# HAN_DE10-Lite_PS2SpeakerShield_001.net
KiCad netlist of a schematic drawn in EAGLE
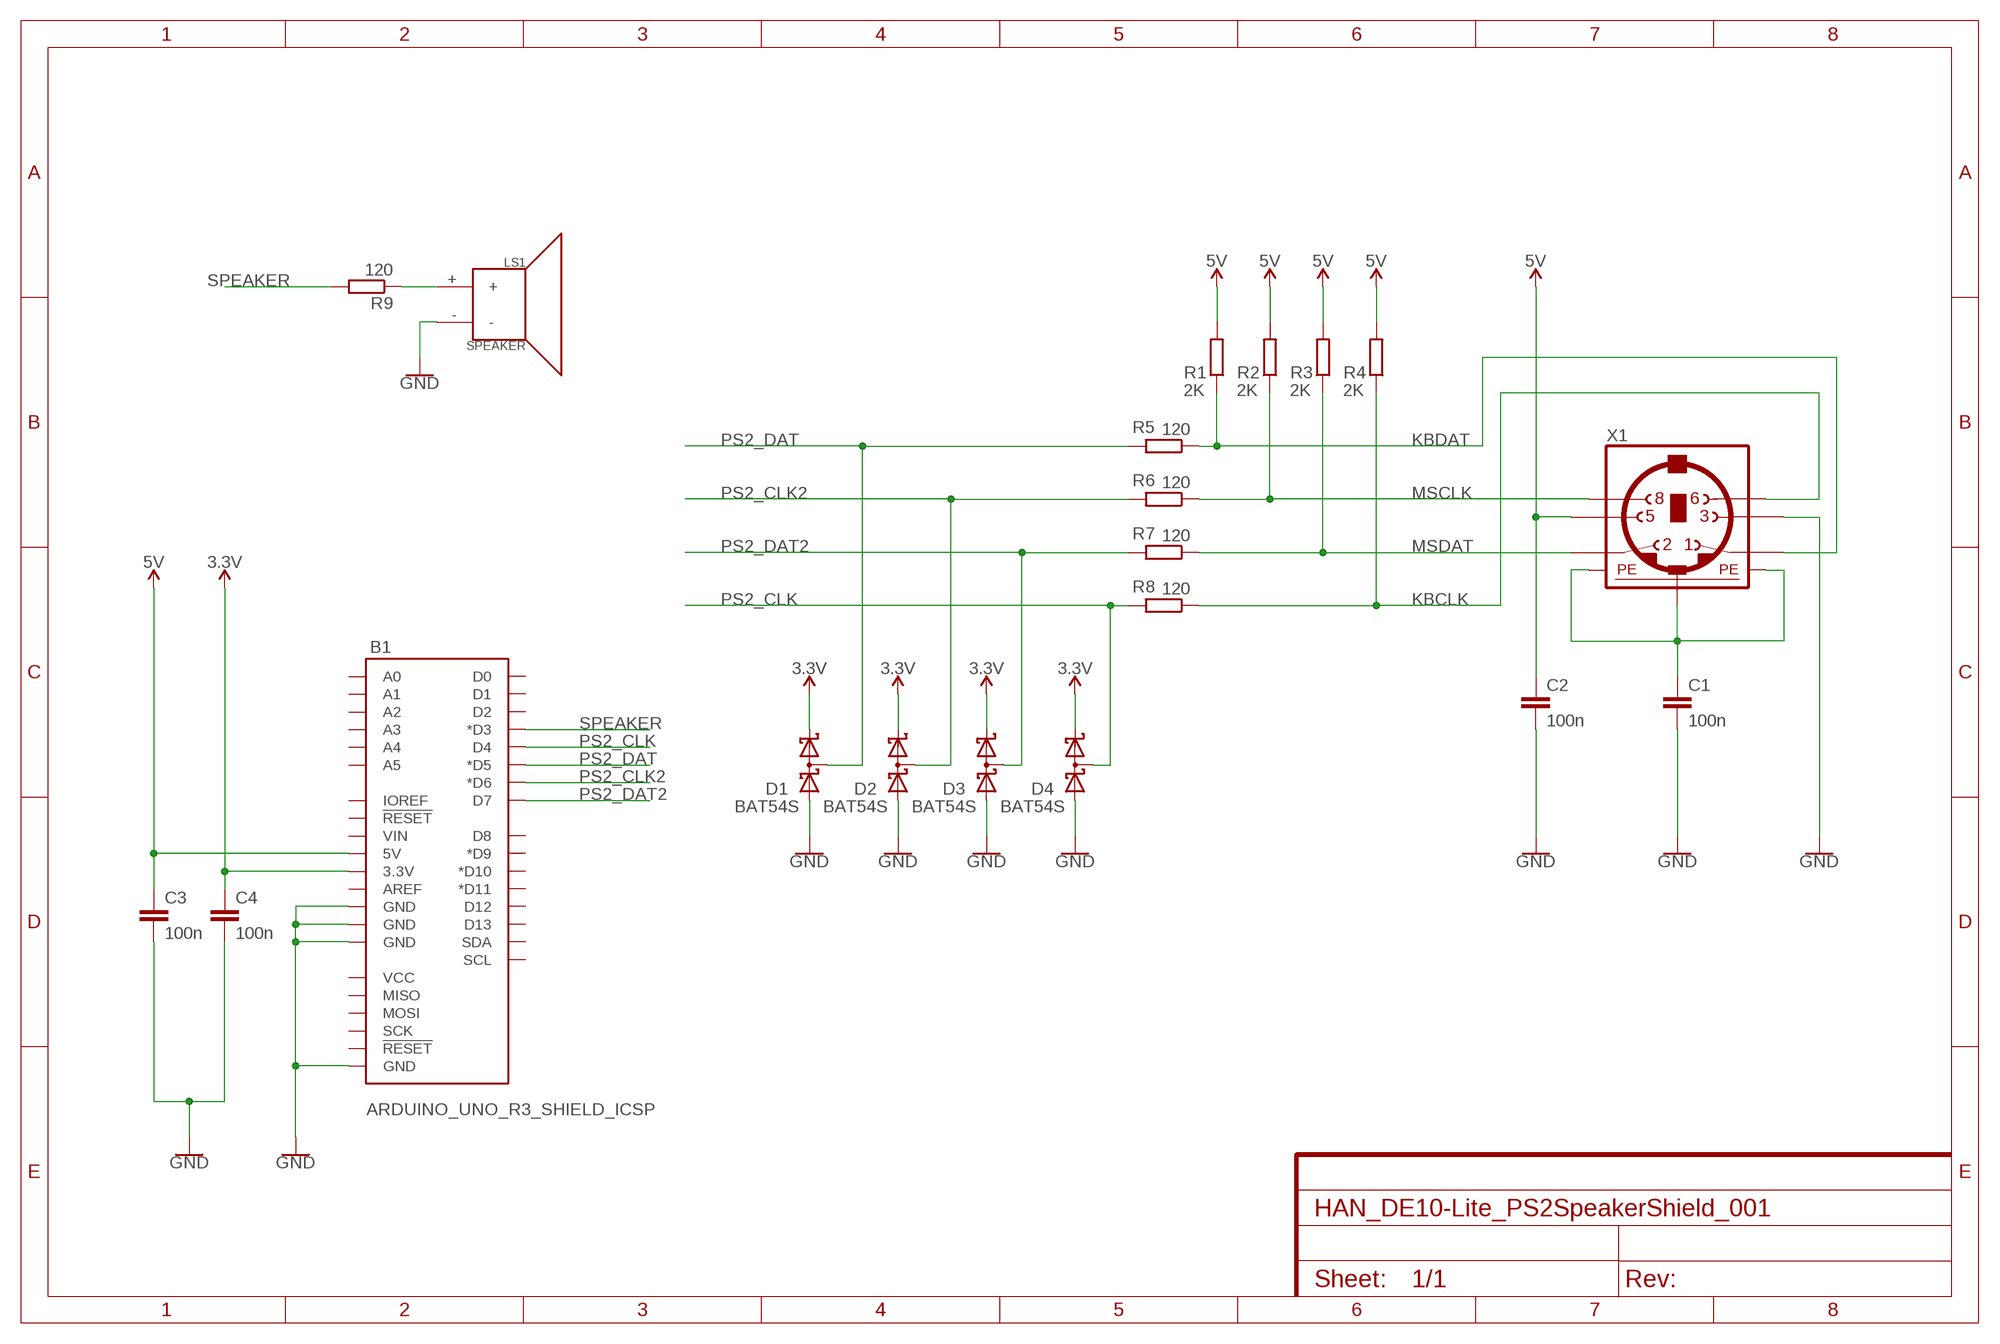
[diagram p0: schematic, sheet 1]

(export (version "E")
  (design (tool "Eeschema 10.0.6"))
  (components
    (comp (ref "B1")
      (value "ARDUINO_UNO_R3_SHIELD_ICSP")
      (footprint "eagle-import:UNO_R3_SHIELD_ICSP")
      (libsource (lib "eagle-import") (part "ARDUINO_UNO_R3_SHIELD_ICSP"))
    )
    (comp (ref "C1")
      (value "100n")
      (footprint "eagle-import:C1206")
      (libsource (lib "eagle-import") (part "C-EUC1206"))
    )
    (comp (ref "C2")
      (value "100n")
      (footprint "eagle-import:C1206")
      (libsource (lib "eagle-import") (part "C-EUC1206"))
    )
    (comp (ref "C3")
      (value "100n")
      (footprint "eagle-import:C1206")
      (libsource (lib "eagle-import") (part "C-EUC1206"))
    )
    (comp (ref "C4")
      (value "100n")
      (footprint "eagle-import:C1206")
      (libsource (lib "eagle-import") (part "C-EUC1206"))
    )
    (comp (ref "D1")
      (value "BAT54S")
      (footprint "eagle-import:SOT23")
      (libsource (lib "eagle-import") (part "BAT54S"))
    )
    (comp (ref "D2")
      (value "BAT54S")
      (footprint "eagle-import:SOT23")
      (libsource (lib "eagle-import") (part "BAT54S"))
    )
    (comp (ref "D3")
      (value "BAT54S")
      (footprint "eagle-import:SOT23")
      (libsource (lib "eagle-import") (part "BAT54S"))
    )
    (comp (ref "D4")
      (value "BAT54S")
      (footprint "eagle-import:SOT23")
      (libsource (lib "eagle-import") (part "BAT54S"))
    )
    (comp (ref "LS1")
      (value "SPEAKER")
      (footprint "eagle-import:PCB_MOUNT_SPEAKER")
      (libsource (lib "eagle-import") (part "SPEAKER"))
    )
    (comp (ref "R1")
      (value "2K")
      (footprint "eagle-import:M1206")
      (libsource (lib "eagle-import") (part "R-EU_M1206"))
    )
    (comp (ref "R2")
      (value "2K")
      (footprint "eagle-import:M1206")
      (libsource (lib "eagle-import") (part "R-EU_M1206"))
    )
    (comp (ref "R3")
      (value "2K")
      (footprint "eagle-import:M1206")
      (libsource (lib "eagle-import") (part "R-EU_M1206"))
    )
    (comp (ref "R4")
      (value "2K")
      (footprint "eagle-import:M1206")
      (libsource (lib "eagle-import") (part "R-EU_M1206"))
    )
    (comp (ref "R5")
      (value "120")
      (footprint "eagle-import:M1206")
      (libsource (lib "eagle-import") (part "R-EU_M1206"))
    )
    (comp (ref "R6")
      (value "120")
      (footprint "eagle-import:M1206")
      (libsource (lib "eagle-import") (part "R-EU_M1206"))
    )
    (comp (ref "R7")
      (value "120")
      (footprint "eagle-import:M1206")
      (libsource (lib "eagle-import") (part "R-EU_M1206"))
    )
    (comp (ref "R8")
      (value "120")
      (footprint "eagle-import:M1206")
      (libsource (lib "eagle-import") (part "R-EU_M1206"))
    )
    (comp (ref "R9")
      (value "120")
      (footprint "eagle-import:M1206")
      (libsource (lib "eagle-import") (part "R-EU_M1206"))
    )
    (comp (ref "X1")
      (value "MINI_DIN_6")
      (footprint "eagle-import:M_DIN6")
      (libsource (lib "eagle-import") (part "MINI_DIN_6"))
    )
  )
  (nets
    (net (code "1") (name "/KBCLK") (class "Default")
      (node (ref "R4") (pin "1") (pinfunction "1_1") (pintype "passive"))
      (node (ref "R8") (pin "1") (pinfunction "1_1") (pintype "passive"))
      (node (ref "X1") (pin "6") (pinfunction "6_6") (pintype "passive"))
    )
    (net (code "2") (name "/KBDAT") (class "Default")
      (node (ref "R1") (pin "1") (pinfunction "1_1") (pintype "passive"))
      (node (ref "R5") (pin "1") (pinfunction "1_1") (pintype "passive"))
      (node (ref "X1") (pin "1") (pinfunction "1_1") (pintype "passive"))
    )
    (net (code "3") (name "/MSCLK") (class "Default")
      (node (ref "R2") (pin "1") (pinfunction "1_1") (pintype "passive"))
      (node (ref "R6") (pin "1") (pinfunction "1_1") (pintype "passive"))
      (node (ref "X1") (pin "8") (pinfunction "8_8") (pintype "passive"))
    )
    (net (code "4") (name "/MSDAT") (class "Default")
      (node (ref "R3") (pin "1") (pinfunction "1_1") (pintype "passive"))
      (node (ref "R7") (pin "1") (pinfunction "1_1") (pintype "passive"))
      (node (ref "X1") (pin "2") (pinfunction "2_2") (pintype "passive"))
    )
    (net (code "5") (name "/PS2_CLK") (class "Default")
      (node (ref "B1") (pin "D4") (pinfunction "D4_D4") (pintype "bidirectional"))
      (node (ref "D4") (pin "3") (pinfunction "K1A2_3") (pintype "passive"))
      (node (ref "R8") (pin "2") (pinfunction "2_2") (pintype "passive"))
    )
    (net (code "6") (name "/PS2_CLK2") (class "Default")
      (node (ref "B1") (pin "D6") (pinfunction "*D6_D6") (pintype "bidirectional"))
      (node (ref "D2") (pin "3") (pinfunction "K1A2_3") (pintype "passive"))
      (node (ref "R6") (pin "2") (pinfunction "2_2") (pintype "passive"))
    )
    (net (code "7") (name "/PS2_DAT") (class "Default")
      (node (ref "B1") (pin "D5") (pinfunction "*D5_D5") (pintype "bidirectional"))
      (node (ref "D1") (pin "3") (pinfunction "K1A2_3") (pintype "passive"))
      (node (ref "R5") (pin "2") (pinfunction "2_2") (pintype "passive"))
    )
    (net (code "8") (name "/PS2_DAT2") (class "Default")
      (node (ref "B1") (pin "D7") (pinfunction "D7_D7") (pintype "bidirectional"))
      (node (ref "D3") (pin "3") (pinfunction "K1A2_3") (pintype "passive"))
      (node (ref "R7") (pin "2") (pinfunction "2_2") (pintype "passive"))
    )
    (net (code "9") (name "/SPEAKER") (class "Default")
      (node (ref "B1") (pin "D3") (pinfunction "*D3_D3") (pintype "bidirectional"))
      (node (ref "R9") (pin "2") (pinfunction "2_2") (pintype "passive"))
    )
    (net (code "10") (name "3.3V") (class "Default")
      (node (ref "B1") (pin "3.3V") (pinfunction "3.3V_3.3V") (pintype "bidirectional"))
      (node (ref "C4") (pin "1") (pinfunction "1_1") (pintype "passive"))
      (node (ref "D1") (pin "2") (pinfunction "K2_2") (pintype "passive"))
      (node (ref "D2") (pin "2") (pinfunction "K2_2") (pintype "passive"))
      (node (ref "D3") (pin "2") (pinfunction "K2_2") (pintype "passive"))
      (node (ref "D4") (pin "2") (pinfunction "K2_2") (pintype "passive"))
    )
    (net (code "11") (name "5V") (class "Default")
      (node (ref "B1") (pin "5V") (pinfunction "5V_5V") (pintype "bidirectional"))
      (node (ref "C2") (pin "1") (pinfunction "1_1") (pintype "passive"))
      (node (ref "C3") (pin "1") (pinfunction "1_1") (pintype "passive"))
      (node (ref "R1") (pin "2") (pinfunction "2_2") (pintype "passive"))
      (node (ref "R2") (pin "2") (pinfunction "2_2") (pintype "passive"))
      (node (ref "R3") (pin "2") (pinfunction "2_2") (pintype "passive"))
      (node (ref "R4") (pin "2") (pinfunction "2_2") (pintype "passive"))
      (node (ref "X1") (pin "5") (pinfunction "5_5") (pintype "passive"))
    )
    (net (code "12") (name "GND") (class "Default")
      (node (ref "B1") (pin "GND@0") (pinfunction "GND_GND@0") (pintype "bidirectional"))
      (node (ref "B1") (pin "GND@1") (pinfunction "GND_GND@1") (pintype "bidirectional"))
      (node (ref "B1") (pin "GND@2") (pinfunction "GND_GND@2") (pintype "bidirectional"))
      (node (ref "B1") (pin "GND_ICSP") (pinfunction "GND_GND_ICSP") (pintype "bidirectional"))
      (node (ref "C1") (pin "2") (pinfunction "2_2") (pintype "passive"))
      (node (ref "C2") (pin "2") (pinfunction "2_2") (pintype "passive"))
      (node (ref "C3") (pin "2") (pinfunction "2_2") (pintype "passive"))
      (node (ref "C4") (pin "2") (pinfunction "2_2") (pintype "passive"))
      (node (ref "D1") (pin "1") (pinfunction "A1_1") (pintype "passive"))
      (node (ref "D2") (pin "1") (pinfunction "A1_1") (pintype "passive"))
      (node (ref "D3") (pin "1") (pinfunction "A1_1") (pintype "passive"))
      (node (ref "D4") (pin "1") (pinfunction "A1_1") (pintype "passive"))
      (node (ref "LS1") (pin "-") (pinfunction "-_-") (pintype "bidirectional"))
      (node (ref "X1") (pin "3") (pinfunction "3_3") (pintype "passive"))
    )
    (net (code "13") (name "Net-(LS1-Pad+)") (class "Default")
      (node (ref "LS1") (pin "+") (pinfunction "+_+") (pintype "bidirectional"))
      (node (ref "R9") (pin "1") (pinfunction "1_1") (pintype "passive"))
    )
    (net (code "14") (name "Net-(X1-PE1)") (class "Default")
      (node (ref "C1") (pin "1") (pinfunction "1_1") (pintype "passive"))
      (node (ref "X1") (pin "SH1") (pinfunction "PE1_SH1") (pintype "power_in"))
      (node (ref "X1") (pin "SH2") (pinfunction "PE2_SH2") (pintype "power_in"))
      (node (ref "X1") (pin "SH3") (pinfunction "PE3_SH3") (pintype "power_in"))
    )
    (net (code "15") (name "unconnected-(B1-*D9-PadD9)") (class "Default")
      (node (ref "B1") (pin "D9") (pinfunction "*D9_D9") (pintype "bidirectional"))
    )
    (net (code "16") (name "unconnected-(B1-*D10-PadD10)") (class "Default")
      (node (ref "B1") (pin "D10") (pinfunction "*D10_D10") (pintype "bidirectional"))
    )
    (net (code "17") (name "unconnected-(B1-*D11-PadD11)") (class "Default")
      (node (ref "B1") (pin "D11") (pinfunction "*D11_D11") (pintype "bidirectional"))
    )
    (net (code "18") (name "unconnected-(B1-D0-PadRX)") (class "Default")
      (node (ref "B1") (pin "RX") (pinfunction "D0_RX") (pintype "bidirectional"))
    )
    (net (code "19") (name "unconnected-(B1-D1-PadTX)") (class "Default")
      (node (ref "B1") (pin "TX") (pinfunction "D1_TX") (pintype "bidirectional"))
    )
    (net (code "20") (name "unconnected-(B1-PadA0)") (class "Default")
      (node (ref "B1") (pin "A0") (pinfunction "A0_A0") (pintype "bidirectional"))
    )
    (net (code "21") (name "unconnected-(B1-PadA1)") (class "Default")
      (node (ref "B1") (pin "A1") (pinfunction "A1_A1") (pintype "bidirectional"))
    )
    (net (code "22") (name "unconnected-(B1-PadA2)") (class "Default")
      (node (ref "B1") (pin "A2") (pinfunction "A2_A2") (pintype "bidirectional"))
    )
    (net (code "23") (name "unconnected-(B1-PadA3)") (class "Default")
      (node (ref "B1") (pin "A3") (pinfunction "A3_A3") (pintype "bidirectional"))
    )
    (net (code "24") (name "unconnected-(B1-PadA4)") (class "Default")
      (node (ref "B1") (pin "A4") (pinfunction "A4_A4") (pintype "bidirectional"))
    )
    (net (code "25") (name "unconnected-(B1-PadA5)") (class "Default")
      (node (ref "B1") (pin "A5") (pinfunction "A5_A5") (pintype "bidirectional"))
    )
    (net (code "26") (name "unconnected-(B1-PadAREF)") (class "Default")
      (node (ref "B1") (pin "AREF") (pinfunction "AREF_AREF") (pintype "bidirectional"))
    )
    (net (code "27") (name "unconnected-(B1-PadD2)") (class "Default")
      (node (ref "B1") (pin "D2") (pinfunction "D2_D2") (pintype "bidirectional"))
    )
    (net (code "28") (name "unconnected-(B1-PadD8)") (class "Default")
      (node (ref "B1") (pin "D8") (pinfunction "D8_D8") (pintype "bidirectional"))
    )
    (net (code "29") (name "unconnected-(B1-PadD12)") (class "Default")
      (node (ref "B1") (pin "D12") (pinfunction "D12_D12") (pintype "bidirectional"))
    )
    (net (code "30") (name "unconnected-(B1-PadD13)") (class "Default")
      (node (ref "B1") (pin "D13") (pinfunction "D13_D13") (pintype "bidirectional"))
    )
    (net (code "31") (name "unconnected-(B1-PadIOREF)") (class "Default")
      (node (ref "B1") (pin "IOREF") (pinfunction "IOREF_IOREF") (pintype "bidirectional"))
    )
    (net (code "32") (name "unconnected-(B1-PadMISO)") (class "Default")
      (node (ref "B1") (pin "MISO") (pinfunction "MISO_MISO") (pintype "bidirectional"))
    )
    (net (code "33") (name "unconnected-(B1-PadMOSI)") (class "Default")
      (node (ref "B1") (pin "MOSI") (pinfunction "MOSI_MOSI") (pintype "bidirectional"))
    )
    (net (code "34") (name "unconnected-(B1-PadSCK)") (class "Default")
      (node (ref "B1") (pin "SCK") (pinfunction "SCK_SCK") (pintype "bidirectional"))
    )
    (net (code "35") (name "unconnected-(B1-PadSCL)") (class "Default")
      (node (ref "B1") (pin "SCL") (pinfunction "SCL_SCL") (pintype "bidirectional"))
    )
    (net (code "36") (name "unconnected-(B1-PadSDA)") (class "Default")
      (node (ref "B1") (pin "SDA") (pinfunction "SDA_SDA") (pintype "bidirectional"))
    )
    (net (code "37") (name "unconnected-(B1-PadVIN)") (class "Default")
      (node (ref "B1") (pin "VIN") (pinfunction "VIN_VIN") (pintype "bidirectional"))
    )
    (net (code "38") (name "unconnected-(B1-VCC-Pad5V_ICSP)") (class "Default")
      (node (ref "B1") (pin "5V_ICSP") (pinfunction "VCC_5V_ICSP") (pintype "bidirectional"))
    )
    (net (code "39") (name "unconnected-(B1-~{RESET}-PadRES)") (class "Default")
      (node (ref "B1") (pin "RES") (pinfunction "~{RESET}_RES") (pintype "bidirectional"))
    )
    (net (code "40") (name "unconnected-(B1-~{RESET}-PadRST_ICSP)") (class "Default")
      (node (ref "B1") (pin "RST_ICSP") (pinfunction "~{RESET}_RST_ICSP") (pintype "bidirectional"))
    )
  )
)
